# UART.net
KiCad netlist of a schematic drawn in Altium Designer
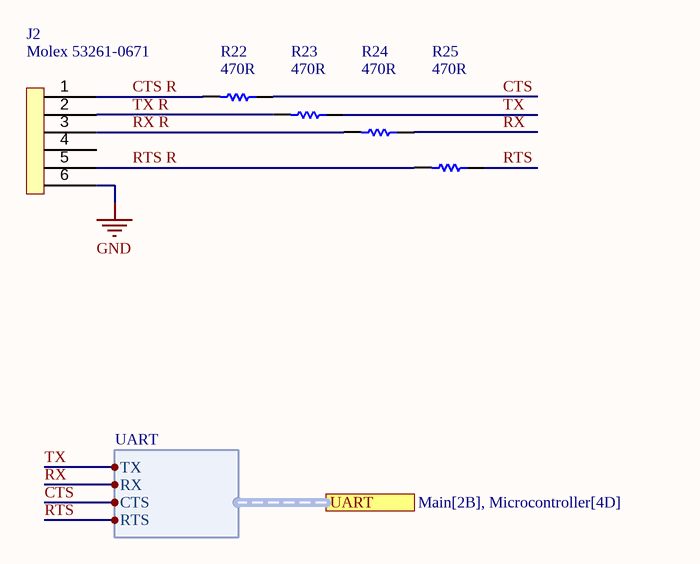
[diagram p0: UART.SchDoc]

(export (version "E")
  (design (tool "Eeschema 10.0.6"))
  (components
    (comp (ref "J2")
      (value "Molex 53261-0671")
      (footprint "Molex 53261-0671")
      (libsource (lib "x-io") (part "Molex 53261-0671"))
    )
    (comp (ref "R22") (value "470R") (footprint "Resistor 0603") (libsource (lib "x-io") (part "Resistor")))
    (comp (ref "R23") (value "470R") (footprint "Resistor 0603") (libsource (lib "x-io") (part "Resistor")))
    (comp (ref "R24") (value "470R") (footprint "Resistor 0603") (libsource (lib "x-io") (part "Resistor")))
    (comp (ref "R25") (value "470R") (footprint "Resistor 0603") (libsource (lib "x-io") (part "Resistor")))
  )
  (nets
    (net (code "2") (name "/CTS") (class "Default")
      (node (ref "R22") (pin "2") (pinfunction "2_2") (pintype "passive"))
    )
    (net (code "3") (name "/CTS R") (class "Default")
      (node (ref "J2") (pin "1") (pinfunction "1_1") (pintype "passive"))
      (node (ref "R22") (pin "1") (pinfunction "1_1") (pintype "passive"))
    )
    (net (code "4") (name "/RTS") (class "Default")
      (node (ref "R25") (pin "2") (pinfunction "2_2") (pintype "passive"))
    )
    (net (code "5") (name "/RTS R") (class "Default")
      (node (ref "J2") (pin "5") (pinfunction "5_5") (pintype "passive"))
      (node (ref "R25") (pin "1") (pinfunction "1_1") (pintype "passive"))
    )
    (net (code "6") (name "/RX") (class "Default")
      (node (ref "R24") (pin "2") (pinfunction "2_2") (pintype "passive"))
    )
    (net (code "7") (name "/RX R") (class "Default")
      (node (ref "J2") (pin "3") (pinfunction "3_3") (pintype "passive"))
      (node (ref "R24") (pin "1") (pinfunction "1_1") (pintype "passive"))
    )
    (net (code "8") (name "/TX") (class "Default")
      (node (ref "R23") (pin "2") (pinfunction "2_2") (pintype "passive"))
    )
    (net (code "9") (name "/TX R") (class "Default")
      (node (ref "J2") (pin "2") (pinfunction "2_2") (pintype "passive"))
      (node (ref "R23") (pin "1") (pinfunction "1_1") (pintype "passive"))
    )
    (net (code "11") (name "GND") (class "Default")
      (node (ref "J2") (pin "6") (pinfunction "6_6") (pintype "passive"))
    )
    (net (code "12") (name "unconnected-(J2-Pad4)") (class "Default")
      (node (ref "J2") (pin "4") (pinfunction "4_4") (pintype "passive"))
    )
  )
)
